# CAN_Interface.net
KiCad netlist of a schematic drawn in Altium Designer
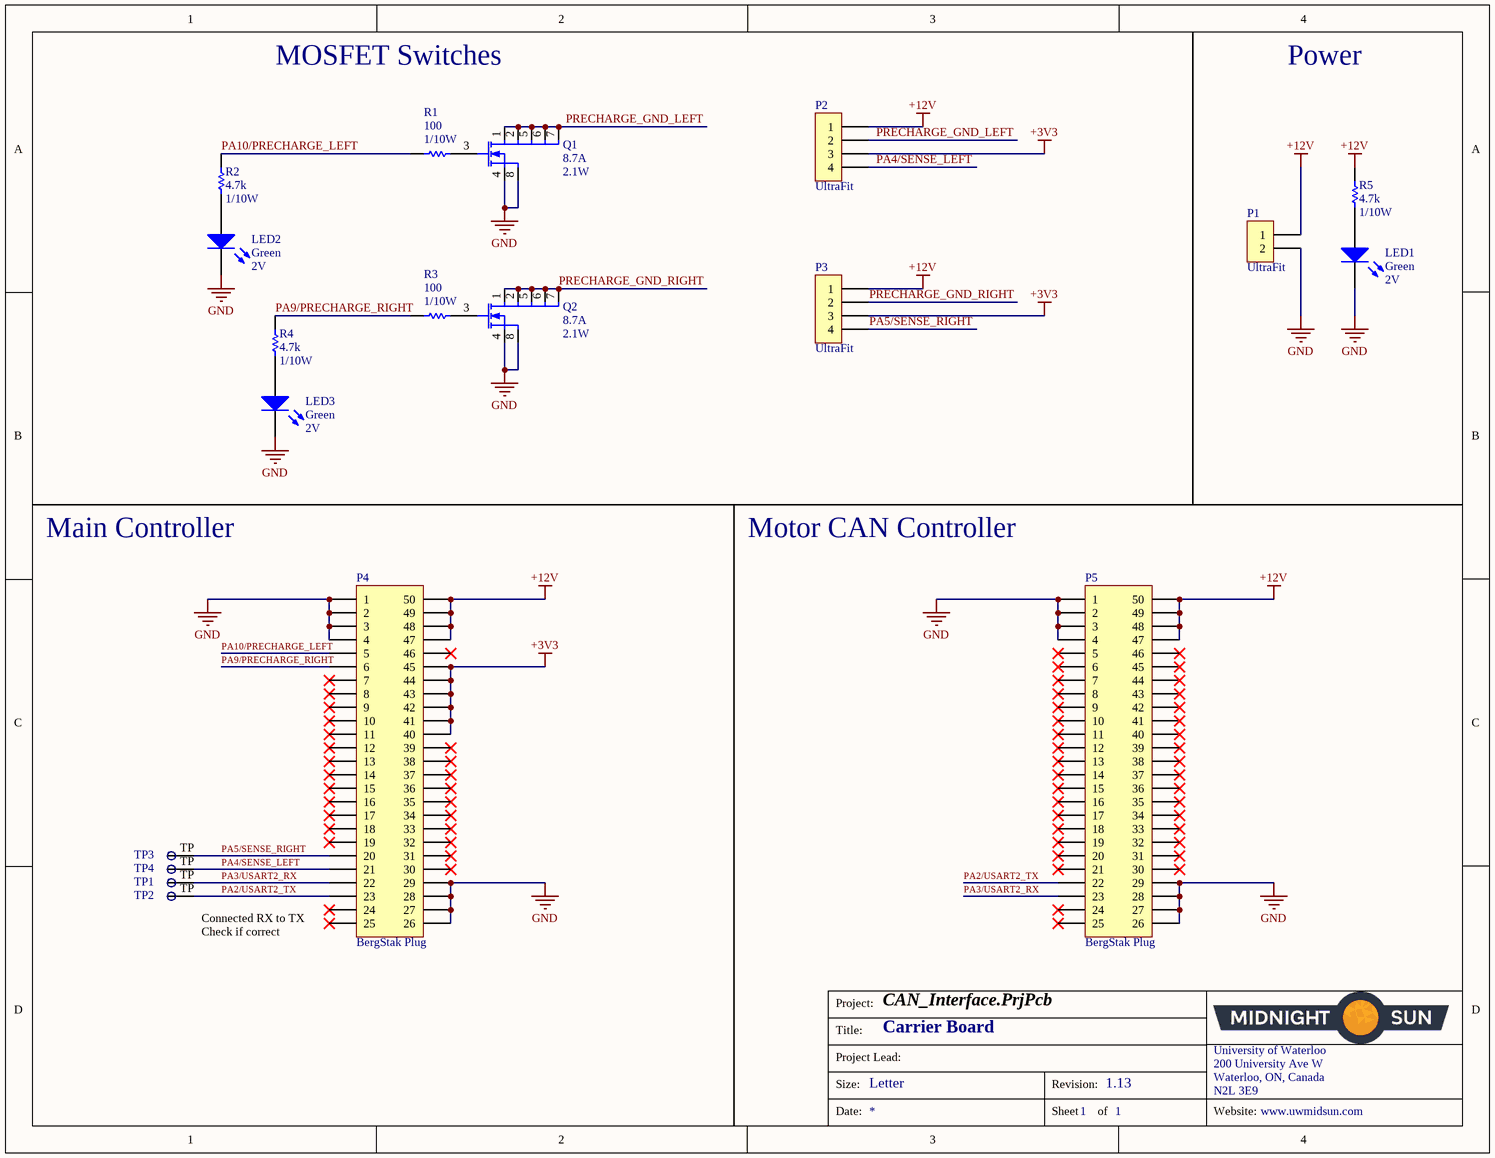
[diagram p0: CAN_Interface.SchDoc]

(export (version "E")
  (design (tool "Eeschema 10.0.6"))
  (components
    (comp (ref "LED1")
      (value "LED GREEN CLEAR 2V 0603")
      (footprint "LED_0603")
      (description "Green 572nm LED Indication - Discrete 2V 0603 (1608 Metric)")
      (fields
        (field (name "MANUFACTURER") "Wurth Electronics Inc.")
        (field (name "MANUFACTURER PART NUMBER") "150060VS75000")
        (field (name "COLOR") "Green")
        (field (name "VOLTAGE - FORWARD (VF) (TYP)") "2V")
      )
      (libsource (lib "Schematic Diagrams") (part "LED GREEN CLEAR 2V 0603"))
    )
    (comp (ref "LED2")
      (value "LED GREEN CLEAR 2V 0603")
      (footprint "LED_0603")
      (description "Green 572nm LED Indication - Discrete 2V 0603 (1608 Metric)")
      (fields
        (field (name "MANUFACTURER") "Wurth Electronics Inc.")
        (field (name "MANUFACTURER PART NUMBER") "150060VS75000")
        (field (name "COLOR") "Green")
        (field (name "VOLTAGE - FORWARD (VF) (TYP)") "2V")
      )
      (libsource (lib "Schematic Diagrams") (part "LED GREEN CLEAR 2V 0603"))
    )
    (comp (ref "LED3")
      (value "LED GREEN CLEAR 2V 0603")
      (footprint "LED_0603")
      (description "Green 572nm LED Indication - Discrete 2V 0603 (1608 Metric)")
      (fields
        (field (name "MANUFACTURER") "Wurth Electronics Inc.")
        (field (name "MANUFACTURER PART NUMBER") "150060VS75000")
        (field (name "COLOR") "Green")
        (field (name "VOLTAGE - FORWARD (VF) (TYP)") "2V")
      )
      (libsource (lib "Schematic Diagrams") (part "LED GREEN CLEAR 2V 0603"))
    )
    (comp (ref "P1")
      (value "CONN 2POS ULTRA-FIT 0.138\"")
      (footprint "CONN, 2POS ULTRA-FIT")
      (description "2 Positions Header, Shrouded Connector 0.138\" (3.50mm) Through Hole Gold")
      (fields (field (name "VOLTAGE") "400V") (field (name "SERIES") "UltraFit"))
      (libsource (lib "Schematic Diagrams") (part "CONN 2POS ULTRA-FIT 0.138{dblquote}"))
    )
    (comp (ref "P2")
      (value "CONN 4POS ULTRA-FIT 0.138\"")
      (footprint "CONN, 4POS ULTRA-FIT")
      (description "4 Positions Header Connector 0.138\" (3.50mm) Through Hole Tin")
      (fields (field (name "VOLTAGE") "400V") (field (name "SERIES") "UltraFit"))
      (libsource (lib "Schematic Diagrams") (part "CONN 4POS ULTRA-FIT 0.138{dblquote}"))
    )
    (comp (ref "P3")
      (value "CONN 4POS ULTRA-FIT 0.138\"")
      (footprint "CONN, 4POS ULTRA-FIT")
      (description "4 Positions Header Connector 0.138\" (3.50mm) Through Hole Tin")
      (fields (field (name "VOLTAGE") "400V") (field (name "SERIES") "UltraFit"))
      (libsource (lib "Schematic Diagrams") (part "CONN 4POS ULTRA-FIT 0.138{dblquote}"))
    )
    (comp (ref "P4")
      (value "CONN 50POS Bergstak Plug 0.02\"")
      (footprint "CONN, Bergstak 50 Pos Plug")
      (description "50 Position Connector Plug, Outer Shroud Contacts Surface Mount Gold")
      (fields (field (name "SERIES") "BergStak Plug"))
      (libsource (lib "Schematic Diagrams") (part "CONN 50POS Bergstak Plug 0.02{dblquote}"))
    )
    (comp (ref "P5")
      (value "CONN 50POS Bergstak Plug 0.02\"")
      (footprint "CONN, Bergstak 50 Pos Plug")
      (description "50 Position Connector Plug, Outer Shroud Contacts Surface Mount Gold")
      (fields (field (name "SERIES") "BergStak Plug"))
      (libsource (lib "Schematic Diagrams") (part "CONN 50POS Bergstak Plug 0.02{dblquote}"))
    )
    (comp (ref "Q1")
      (value "MOSFET N-CH 30V 8.7A 2.1W 6-PQFN (2x2)")
      (footprint "MOSFET N-CH 30V 12A 2mmx2mm PQFN")
      (fields
        (field (name "CURRENT - CONTINUOUS DRAIN (ID) @ 25°C") "8.7A")
        (field (name "POWER DISSIPATION (MAX)") "2.1W")
      )
      (libsource (lib "Schematic Diagrams") (part "MOSFET N-CH 30V 8.7A 2.1W 6-PQFN (2x2)"))
    )
    (comp (ref "Q2")
      (value "MOSFET N-CH 30V 8.7A 2.1W 6-PQFN (2x2)")
      (footprint "MOSFET N-CH 30V 12A 2mmx2mm PQFN")
      (fields
        (field (name "CURRENT - CONTINUOUS DRAIN (ID) @ 25°C") "8.7A")
        (field (name "POWER DISSIPATION (MAX)") "2.1W")
      )
      (libsource (lib "Schematic Diagrams") (part "MOSFET N-CH 30V 8.7A 2.1W 6-PQFN (2x2)"))
    )
    (comp (ref "R1")
      (value "RES 100 OHM 1% 1/10W 0603")
      (footprint "RES, 0603")
      (description "100 Ohm ±1% 0.1W, 1/10W Chip Resistor 0603 (1608 Metric) Moisture Resistant Thick Film")
      (fields
        (field (name "TOLERANCE") "±1%")
        (field (name "RESISTANCE") "100")
        (field (name "POWER") "1/10W")
      )
      (libsource (lib "Schematic Diagrams") (part "RES 100 OHM 1% 1/10W 0603"))
    )
    (comp (ref "R2")
      (value "RES 4.7K OHM 1% 1/10W 0603")
      (footprint "RES, 0603")
      (description "4.7k Ohm ±1% 0.1W, 1/10W Chip Resistor 0603 (1608 Metric) Moisture Resistant Thick Film")
      (fields
        (field (name "TOLERANCE") "±1%")
        (field (name "RESISTANCE (OHMS)") "4.7k")
        (field (name "POWER (WATTS)") "1/10W")
      )
      (libsource (lib "Schematic Diagrams") (part "RES 4.7K OHM 1% 1/10W 0603"))
    )
    (comp (ref "R3")
      (value "RES 100 OHM 1% 1/10W 0603")
      (footprint "RES, 0603")
      (description "100 Ohm ±1% 0.1W, 1/10W Chip Resistor 0603 (1608 Metric) Moisture Resistant Thick Film")
      (fields
        (field (name "TOLERANCE") "±1%")
        (field (name "RESISTANCE") "100")
        (field (name "POWER") "1/10W")
      )
      (libsource (lib "Schematic Diagrams") (part "RES 100 OHM 1% 1/10W 0603"))
    )
    (comp (ref "R4")
      (value "RES 4.7K OHM 1% 1/10W 0603")
      (footprint "RES, 0603")
      (description "4.7k Ohm ±1% 0.1W, 1/10W Chip Resistor 0603 (1608 Metric) Moisture Resistant Thick Film")
      (fields
        (field (name "TOLERANCE") "±1%")
        (field (name "RESISTANCE (OHMS)") "4.7k")
        (field (name "POWER (WATTS)") "1/10W")
      )
      (libsource (lib "Schematic Diagrams") (part "RES 4.7K OHM 1% 1/10W 0603"))
    )
    (comp (ref "R5")
      (value "RES 4.7K OHM 1% 1/10W 0603")
      (footprint "RES, 0603")
      (description "4.7k Ohm ±1% 0.1W, 1/10W Chip Resistor 0603 (1608 Metric) Moisture Resistant Thick Film")
      (fields
        (field (name "TOLERANCE") "±1%")
        (field (name "RESISTANCE (OHMS)") "4.7k")
        (field (name "POWER (WATTS)") "1/10W")
      )
      (libsource (lib "Schematic Diagrams") (part "RES 4.7K OHM 1% 1/10W 0603"))
    )
    (comp (ref "TP1")
      (value "USART2_RX")
      (footprint "Test Point")
      (libsource (lib "Schematic Diagrams") (part "Test Point"))
    )
    (comp (ref "TP2")
      (value "USART2_TX")
      (footprint "Test Point")
      (libsource (lib "Schematic Diagrams") (part "Test Point"))
    )
    (comp (ref "TP3")
      (value "SENSE_RIGHT")
      (footprint "Test Point")
      (libsource (lib "Schematic Diagrams") (part "Test Point"))
    )
    (comp (ref "TP4")
      (value "SENSE_LEFT")
      (footprint "Test Point")
      (libsource (lib "Schematic Diagrams") (part "Test Point"))
    )
  )
  (nets
    (net (code "1") (name "+3V3") (class "Default")
      (node (ref "P2") (pin "3") (pinfunction "3_3") (pintype "passive"))
      (node (ref "P3") (pin "3") (pinfunction "3_3") (pintype "passive"))
      (node (ref "P4") (pin "40") (pinfunction "40_40") (pintype "passive"))
      (node (ref "P4") (pin "41") (pinfunction "41_41") (pintype "passive"))
      (node (ref "P4") (pin "42") (pinfunction "42_42") (pintype "passive"))
      (node (ref "P4") (pin "43") (pinfunction "43_43") (pintype "passive"))
      (node (ref "P4") (pin "44") (pinfunction "44_44") (pintype "passive"))
      (node (ref "P4") (pin "45") (pinfunction "45_45") (pintype "passive"))
    )
    (net (code "2") (name "+12V") (class "Default")
      (node (ref "P1") (pin "1") (pinfunction "1_1") (pintype "passive"))
      (node (ref "P2") (pin "1") (pinfunction "1_1") (pintype "passive"))
      (node (ref "P3") (pin "1") (pinfunction "1_1") (pintype "passive"))
      (node (ref "P4") (pin "47") (pinfunction "47_47") (pintype "passive"))
      (node (ref "P4") (pin "48") (pinfunction "48_48") (pintype "passive"))
      (node (ref "P4") (pin "49") (pinfunction "49_49") (pintype "passive"))
      (node (ref "P4") (pin "50") (pinfunction "50_50") (pintype "passive"))
      (node (ref "P5") (pin "47") (pinfunction "47_47") (pintype "passive"))
      (node (ref "P5") (pin "48") (pinfunction "48_48") (pintype "passive"))
      (node (ref "P5") (pin "49") (pinfunction "49_49") (pintype "passive"))
      (node (ref "P5") (pin "50") (pinfunction "50_50") (pintype "passive"))
      (node (ref "R5") (pin "1") (pinfunction "1_1") (pintype "passive"))
    )
    (net (code "3") (name "/PA2{slash}USART2_TX") (class "Default")
      (node (ref "P4") (pin "23") (pinfunction "23_23") (pintype "passive"))
      (node (ref "P5") (pin "22") (pinfunction "22_22") (pintype "passive"))
      (node (ref "TP2") (pin "TP") (pinfunction "1_TP") (pintype "passive"))
    )
    (net (code "4") (name "/PA3{slash}USART2_RX") (class "Default")
      (node (ref "P4") (pin "22") (pinfunction "22_22") (pintype "passive"))
      (node (ref "P5") (pin "23") (pinfunction "23_23") (pintype "passive"))
      (node (ref "TP1") (pin "TP") (pinfunction "1_TP") (pintype "passive"))
    )
    (net (code "5") (name "/PA4{slash}SENSE_LEFT") (class "Default")
      (node (ref "P2") (pin "4") (pinfunction "4_4") (pintype "passive"))
      (node (ref "P4") (pin "21") (pinfunction "21_21") (pintype "passive"))
      (node (ref "TP4") (pin "TP") (pinfunction "1_TP") (pintype "passive"))
    )
    (net (code "6") (name "/PA5{slash}SENSE_RIGHT") (class "Default")
      (node (ref "P3") (pin "4") (pinfunction "4_4") (pintype "passive"))
      (node (ref "P4") (pin "20") (pinfunction "20_20") (pintype "passive"))
      (node (ref "TP3") (pin "TP") (pinfunction "1_TP") (pintype "passive"))
    )
    (net (code "7") (name "/PA9{slash}PRECHARGE_RIGHT") (class "Default")
      (node (ref "P4") (pin "6") (pinfunction "6_6") (pintype "passive"))
      (node (ref "R3") (pin "1") (pinfunction "1_1") (pintype "passive"))
      (node (ref "R4") (pin "1") (pinfunction "1_1") (pintype "passive"))
    )
    (net (code "8") (name "/PA10{slash}PRECHARGE_LEFT") (class "Default")
      (node (ref "P4") (pin "5") (pinfunction "5_5") (pintype "passive"))
      (node (ref "R1") (pin "1") (pinfunction "1_1") (pintype "passive"))
      (node (ref "R2") (pin "1") (pinfunction "1_1") (pintype "passive"))
    )
    (net (code "9") (name "/PRECHARGE_GND_LEFT") (class "Default")
      (node (ref "P2") (pin "2") (pinfunction "2_2") (pintype "passive"))
      (node (ref "Q1") (pin "1") (pinfunction "D_1") (pintype "passive"))
      (node (ref "Q1") (pin "2") (pinfunction "D_2") (pintype "passive"))
      (node (ref "Q1") (pin "5") (pinfunction "D_5") (pintype "passive"))
      (node (ref "Q1") (pin "6") (pinfunction "D_6") (pintype "passive"))
      (node (ref "Q1") (pin "7") (pinfunction "D_7") (pintype "passive"))
    )
    (net (code "10") (name "/PRECHARGE_GND_RIGHT") (class "Default")
      (node (ref "P3") (pin "2") (pinfunction "2_2") (pintype "passive"))
      (node (ref "Q2") (pin "1") (pinfunction "D_1") (pintype "passive"))
      (node (ref "Q2") (pin "2") (pinfunction "D_2") (pintype "passive"))
      (node (ref "Q2") (pin "5") (pinfunction "D_5") (pintype "passive"))
      (node (ref "Q2") (pin "6") (pinfunction "D_6") (pintype "passive"))
      (node (ref "Q2") (pin "7") (pinfunction "D_7") (pintype "passive"))
    )
    (net (code "11") (name "GND") (class "Default")
      (node (ref "LED1") (pin "2") (pinfunction "K_2") (pintype "passive"))
      (node (ref "LED2") (pin "2") (pinfunction "K_2") (pintype "passive"))
      (node (ref "LED3") (pin "2") (pinfunction "K_2") (pintype "passive"))
      (node (ref "P1") (pin "2") (pinfunction "2_2") (pintype "passive"))
      (node (ref "P4") (pin "1") (pinfunction "1_1") (pintype "passive"))
      (node (ref "P4") (pin "2") (pinfunction "2_2") (pintype "passive"))
      (node (ref "P4") (pin "26") (pinfunction "26_26") (pintype "passive"))
      (node (ref "P4") (pin "27") (pinfunction "27_27") (pintype "passive"))
      (node (ref "P4") (pin "28") (pinfunction "28_28") (pintype "passive"))
      (node (ref "P4") (pin "29") (pinfunction "29_29") (pintype "passive"))
      (node (ref "P4") (pin "3") (pinfunction "3_3") (pintype "passive"))
      (node (ref "P4") (pin "4") (pinfunction "4_4") (pintype "passive"))
      (node (ref "P5") (pin "1") (pinfunction "1_1") (pintype "passive"))
      (node (ref "P5") (pin "2") (pinfunction "2_2") (pintype "passive"))
      (node (ref "P5") (pin "26") (pinfunction "26_26") (pintype "passive"))
      (node (ref "P5") (pin "27") (pinfunction "27_27") (pintype "passive"))
      (node (ref "P5") (pin "28") (pinfunction "28_28") (pintype "passive"))
      (node (ref "P5") (pin "29") (pinfunction "29_29") (pintype "passive"))
      (node (ref "P5") (pin "3") (pinfunction "3_3") (pintype "passive"))
      (node (ref "P5") (pin "4") (pinfunction "4_4") (pintype "passive"))
      (node (ref "Q1") (pin "4") (pinfunction "S_4") (pintype "passive"))
      (node (ref "Q1") (pin "8") (pinfunction "S_8") (pintype "passive"))
      (node (ref "Q2") (pin "4") (pinfunction "S_4") (pintype "passive"))
      (node (ref "Q2") (pin "8") (pinfunction "S_8") (pintype "passive"))
    )
    (net (code "12") (name "Net-(LED1-A)") (class "Default")
      (node (ref "LED1") (pin "1") (pinfunction "A_1") (pintype "passive"))
      (node (ref "R5") (pin "2") (pinfunction "2_2") (pintype "passive"))
    )
    (net (code "13") (name "Net-(LED2-A)") (class "Default")
      (node (ref "LED2") (pin "1") (pinfunction "A_1") (pintype "passive"))
      (node (ref "R2") (pin "2") (pinfunction "2_2") (pintype "passive"))
    )
    (net (code "14") (name "Net-(LED3-A)") (class "Default")
      (node (ref "LED3") (pin "1") (pinfunction "A_1") (pintype "passive"))
      (node (ref "R4") (pin "2") (pinfunction "2_2") (pintype "passive"))
    )
    (net (code "15") (name "Net-(Q1-G)") (class "Default")
      (node (ref "Q1") (pin "3") (pinfunction "G_3") (pintype "passive"))
      (node (ref "R1") (pin "2") (pinfunction "2_2") (pintype "passive"))
    )
    (net (code "16") (name "Net-(Q2-G)") (class "Default")
      (node (ref "Q2") (pin "3") (pinfunction "G_3") (pintype "passive"))
      (node (ref "R3") (pin "2") (pinfunction "2_2") (pintype "passive"))
    )
    (net (code "17") (name "unconnected-(P4-Pad7)") (class "Default")
      (node (ref "P4") (pin "7") (pinfunction "7_7") (pintype "passive+no_connect"))
    )
    (net (code "18") (name "unconnected-(P4-Pad8)") (class "Default")
      (node (ref "P4") (pin "8") (pinfunction "8_8") (pintype "passive+no_connect"))
    )
    (net (code "19") (name "unconnected-(P4-Pad9)") (class "Default")
      (node (ref "P4") (pin "9") (pinfunction "9_9") (pintype "passive+no_connect"))
    )
    (net (code "20") (name "unconnected-(P4-Pad10)") (class "Default")
      (node (ref "P4") (pin "10") (pinfunction "10_10") (pintype "passive+no_connect"))
    )
    (net (code "21") (name "unconnected-(P4-Pad11)") (class "Default")
      (node (ref "P4") (pin "11") (pinfunction "11_11") (pintype "passive+no_connect"))
    )
    (net (code "22") (name "unconnected-(P4-Pad12)") (class "Default")
      (node (ref "P4") (pin "12") (pinfunction "12_12") (pintype "passive+no_connect"))
    )
    (net (code "23") (name "unconnected-(P4-Pad13)") (class "Default")
      (node (ref "P4") (pin "13") (pinfunction "13_13") (pintype "passive+no_connect"))
    )
    (net (code "24") (name "unconnected-(P4-Pad14)") (class "Default")
      (node (ref "P4") (pin "14") (pinfunction "14_14") (pintype "passive+no_connect"))
    )
    (net (code "25") (name "unconnected-(P4-Pad15)") (class "Default")
      (node (ref "P4") (pin "15") (pinfunction "15_15") (pintype "passive+no_connect"))
    )
    (net (code "26") (name "unconnected-(P4-Pad16)") (class "Default")
      (node (ref "P4") (pin "16") (pinfunction "16_16") (pintype "passive+no_connect"))
    )
    (net (code "27") (name "unconnected-(P4-Pad17)") (class "Default")
      (node (ref "P4") (pin "17") (pinfunction "17_17") (pintype "passive+no_connect"))
    )
    (net (code "28") (name "unconnected-(P4-Pad18)") (class "Default")
      (node (ref "P4") (pin "18") (pinfunction "18_18") (pintype "passive+no_connect"))
    )
    (net (code "29") (name "unconnected-(P4-Pad19)") (class "Default")
      (node (ref "P4") (pin "19") (pinfunction "19_19") (pintype "passive+no_connect"))
    )
    (net (code "30") (name "unconnected-(P4-Pad24)") (class "Default")
      (node (ref "P4") (pin "24") (pinfunction "24_24") (pintype "passive+no_connect"))
    )
    (net (code "31") (name "unconnected-(P4-Pad25)") (class "Default")
      (node (ref "P4") (pin "25") (pinfunction "25_25") (pintype "passive+no_connect"))
    )
    (net (code "32") (name "unconnected-(P4-Pad30)") (class "Default")
      (node (ref "P4") (pin "30") (pinfunction "30_30") (pintype "passive+no_connect"))
    )
    (net (code "33") (name "unconnected-(P4-Pad31)") (class "Default")
      (node (ref "P4") (pin "31") (pinfunction "31_31") (pintype "passive+no_connect"))
    )
    (net (code "34") (name "unconnected-(P4-Pad32)") (class "Default")
      (node (ref "P4") (pin "32") (pinfunction "32_32") (pintype "passive+no_connect"))
    )
    (net (code "35") (name "unconnected-(P4-Pad33)") (class "Default")
      (node (ref "P4") (pin "33") (pinfunction "33_33") (pintype "passive+no_connect"))
    )
    (net (code "36") (name "unconnected-(P4-Pad34)") (class "Default")
      (node (ref "P4") (pin "34") (pinfunction "34_34") (pintype "passive+no_connect"))
    )
    (net (code "37") (name "unconnected-(P4-Pad35)") (class "Default")
      (node (ref "P4") (pin "35") (pinfunction "35_35") (pintype "passive+no_connect"))
    )
    (net (code "38") (name "unconnected-(P4-Pad36)") (class "Default")
      (node (ref "P4") (pin "36") (pinfunction "36_36") (pintype "passive+no_connect"))
    )
    (net (code "39") (name "unconnected-(P4-Pad37)") (class "Default")
      (node (ref "P4") (pin "37") (pinfunction "37_37") (pintype "passive+no_connect"))
    )
    (net (code "40") (name "unconnected-(P4-Pad38)") (class "Default")
      (node (ref "P4") (pin "38") (pinfunction "38_38") (pintype "passive+no_connect"))
    )
    (net (code "41") (name "unconnected-(P4-Pad39)") (class "Default")
      (node (ref "P4") (pin "39") (pinfunction "39_39") (pintype "passive+no_connect"))
    )
    (net (code "42") (name "unconnected-(P4-Pad46)") (class "Default")
      (node (ref "P4") (pin "46") (pinfunction "46_46") (pintype "passive+no_connect"))
    )
    (net (code "43") (name "unconnected-(P5-Pad5)") (class "Default")
      (node (ref "P5") (pin "5") (pinfunction "5_5") (pintype "passive+no_connect"))
    )
    (net (code "44") (name "unconnected-(P5-Pad6)") (class "Default")
      (node (ref "P5") (pin "6") (pinfunction "6_6") (pintype "passive+no_connect"))
    )
    (net (code "45") (name "unconnected-(P5-Pad7)") (class "Default")
      (node (ref "P5") (pin "7") (pinfunction "7_7") (pintype "passive+no_connect"))
    )
    (net (code "46") (name "unconnected-(P5-Pad8)") (class "Default")
      (node (ref "P5") (pin "8") (pinfunction "8_8") (pintype "passive+no_connect"))
    )
    (net (code "47") (name "unconnected-(P5-Pad9)") (class "Default")
      (node (ref "P5") (pin "9") (pinfunction "9_9") (pintype "passive+no_connect"))
    )
    (net (code "48") (name "unconnected-(P5-Pad10)") (class "Default")
      (node (ref "P5") (pin "10") (pinfunction "10_10") (pintype "passive+no_connect"))
    )
    (net (code "49") (name "unconnected-(P5-Pad11)") (class "Default")
      (node (ref "P5") (pin "11") (pinfunction "11_11") (pintype "passive+no_connect"))
    )
    (net (code "50") (name "unconnected-(P5-Pad12)") (class "Default")
      (node (ref "P5") (pin "12") (pinfunction "12_12") (pintype "passive+no_connect"))
    )
    (net (code "51") (name "unconnected-(P5-Pad13)") (class "Default")
      (node (ref "P5") (pin "13") (pinfunction "13_13") (pintype "passive+no_connect"))
    )
    (net (code "52") (name "unconnected-(P5-Pad14)") (class "Default")
      (node (ref "P5") (pin "14") (pinfunction "14_14") (pintype "passive+no_connect"))
    )
    (net (code "53") (name "unconnected-(P5-Pad15)") (class "Default")
      (node (ref "P5") (pin "15") (pinfunction "15_15") (pintype "passive+no_connect"))
    )
    (net (code "54") (name "unconnected-(P5-Pad16)") (class "Default")
      (node (ref "P5") (pin "16") (pinfunction "16_16") (pintype "passive+no_connect"))
    )
    (net (code "55") (name "unconnected-(P5-Pad17)") (class "Default")
      (node (ref "P5") (pin "17") (pinfunction "17_17") (pintype "passive+no_connect"))
    )
    (net (code "56") (name "unconnected-(P5-Pad18)") (class "Default")
      (node (ref "P5") (pin "18") (pinfunction "18_18") (pintype "passive+no_connect"))
    )
    (net (code "57") (name "unconnected-(P5-Pad19)") (class "Default")
      (node (ref "P5") (pin "19") (pinfunction "19_19") (pintype "passive+no_connect"))
    )
    (net (code "58") (name "unconnected-(P5-Pad20)") (class "Default")
      (node (ref "P5") (pin "20") (pinfunction "20_20") (pintype "passive+no_connect"))
    )
    (net (code "59") (name "unconnected-(P5-Pad21)") (class "Default")
      (node (ref "P5") (pin "21") (pinfunction "21_21") (pintype "passive+no_connect"))
    )
    (net (code "60") (name "unconnected-(P5-Pad24)") (class "Default")
      (node (ref "P5") (pin "24") (pinfunction "24_24") (pintype "passive+no_connect"))
    )
    (net (code "61") (name "unconnected-(P5-Pad25)") (class "Default")
      (node (ref "P5") (pin "25") (pinfunction "25_25") (pintype "passive+no_connect"))
    )
    (net (code "62") (name "unconnected-(P5-Pad30)") (class "Default")
      (node (ref "P5") (pin "30") (pinfunction "30_30") (pintype "passive+no_connect"))
    )
    (net (code "63") (name "unconnected-(P5-Pad31)") (class "Default")
      (node (ref "P5") (pin "31") (pinfunction "31_31") (pintype "passive+no_connect"))
    )
    (net (code "64") (name "unconnected-(P5-Pad32)") (class "Default")
      (node (ref "P5") (pin "32") (pinfunction "32_32") (pintype "passive+no_connect"))
    )
    (net (code "65") (name "unconnected-(P5-Pad33)") (class "Default")
      (node (ref "P5") (pin "33") (pinfunction "33_33") (pintype "passive+no_connect"))
    )
    (net (code "66") (name "unconnected-(P5-Pad34)") (class "Default")
      (node (ref "P5") (pin "34") (pinfunction "34_34") (pintype "passive+no_connect"))
    )
    (net (code "67") (name "unconnected-(P5-Pad35)") (class "Default")
      (node (ref "P5") (pin "35") (pinfunction "35_35") (pintype "passive+no_connect"))
    )
    (net (code "68") (name "unconnected-(P5-Pad36)") (class "Default")
      (node (ref "P5") (pin "36") (pinfunction "36_36") (pintype "passive+no_connect"))
    )
    (net (code "69") (name "unconnected-(P5-Pad37)") (class "Default")
      (node (ref "P5") (pin "37") (pinfunction "37_37") (pintype "passive+no_connect"))
    )
    (net (code "70") (name "unconnected-(P5-Pad38)") (class "Default")
      (node (ref "P5") (pin "38") (pinfunction "38_38") (pintype "passive+no_connect"))
    )
    (net (code "71") (name "unconnected-(P5-Pad39)") (class "Default")
      (node (ref "P5") (pin "39") (pinfunction "39_39") (pintype "passive+no_connect"))
    )
    (net (code "72") (name "unconnected-(P5-Pad40)") (class "Default")
      (node (ref "P5") (pin "40") (pinfunction "40_40") (pintype "passive+no_connect"))
    )
    (net (code "73") (name "unconnected-(P5-Pad41)") (class "Default")
      (node (ref "P5") (pin "41") (pinfunction "41_41") (pintype "passive+no_connect"))
    )
    (net (code "74") (name "unconnected-(P5-Pad42)") (class "Default")
      (node (ref "P5") (pin "42") (pinfunction "42_42") (pintype "passive+no_connect"))
    )
    (net (code "75") (name "unconnected-(P5-Pad43)") (class "Default")
      (node (ref "P5") (pin "43") (pinfunction "43_43") (pintype "passive+no_connect"))
    )
    (net (code "76") (name "unconnected-(P5-Pad44)") (class "Default")
      (node (ref "P5") (pin "44") (pinfunction "44_44") (pintype "passive+no_connect"))
    )
    (net (code "77") (name "unconnected-(P5-Pad45)") (class "Default")
      (node (ref "P5") (pin "45") (pinfunction "45_45") (pintype "passive+no_connect"))
    )
    (net (code "78") (name "unconnected-(P5-Pad46)") (class "Default")
      (node (ref "P5") (pin "46") (pinfunction "46_46") (pintype "passive+no_connect"))
    )
  )
)
